# SCH_CPU.net
KiCad netlist of a schematic drawn in Altium Designer
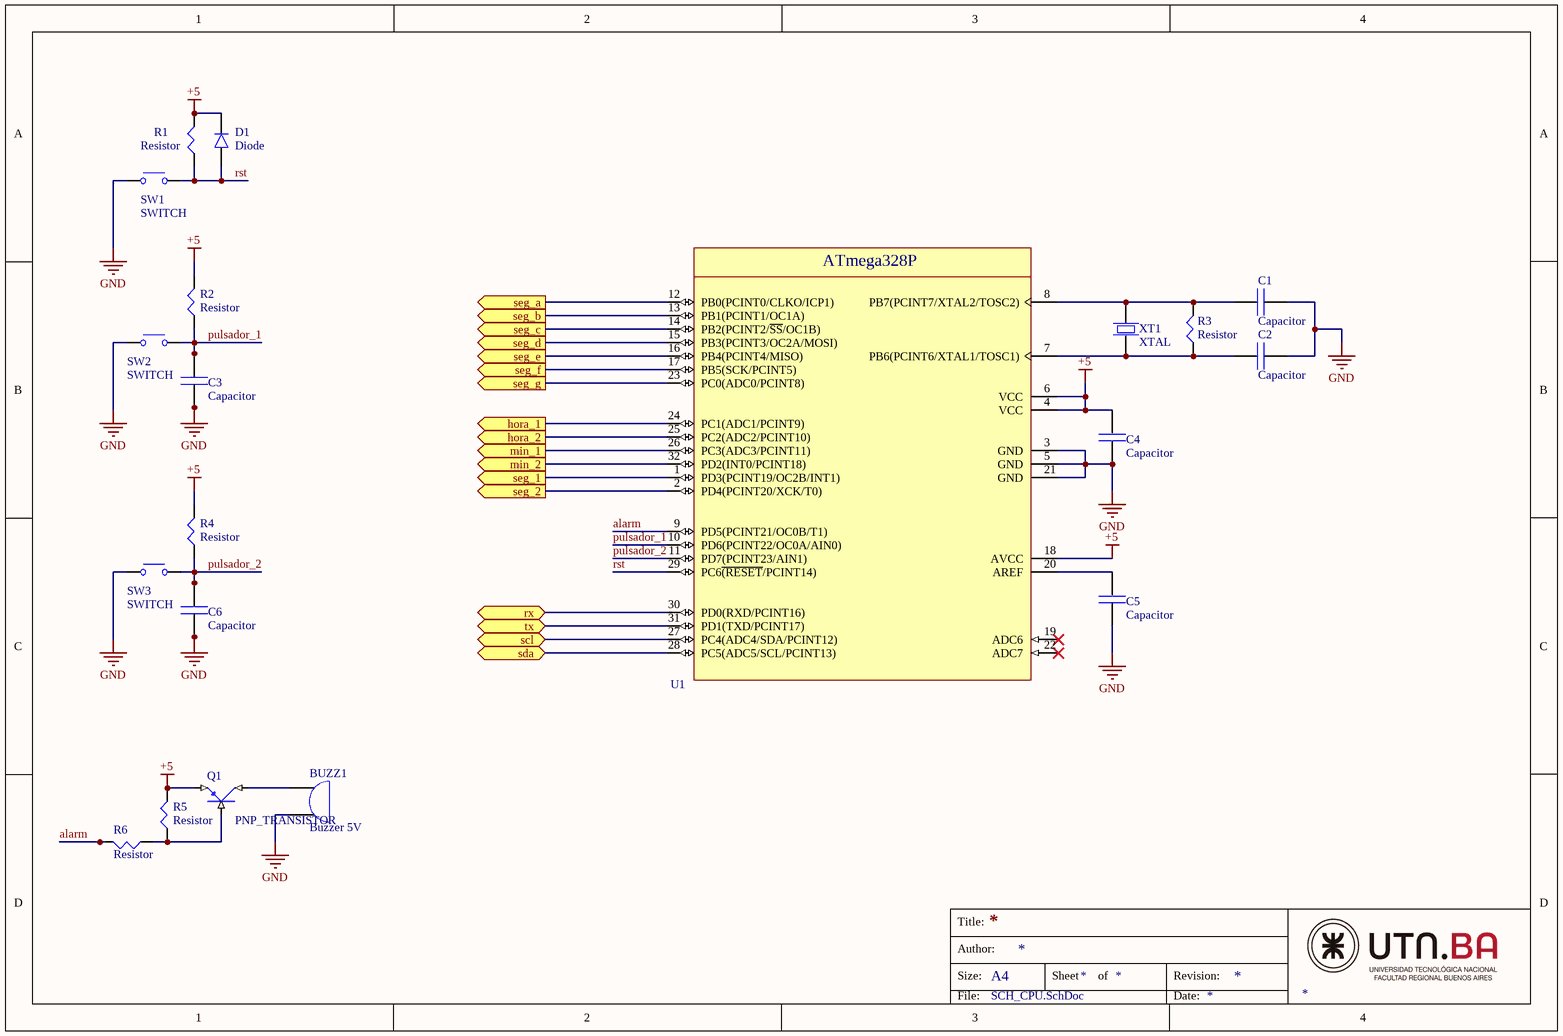
[diagram p0: SCH_CPU.SchDoc]

(export (version "E")
  (design (tool "Eeschema 10.0.6"))
  (components
    (comp (ref "BUZZ1") (value "Buzzer 5V") (libsource (lib "SCH_LIB") (part "Buzzer")))
    (comp (ref "C1")
      (value "Capacitor")
      (description "100nF x 50v")
      (libsource (lib "SCH_LIB") (part "Capacitor"))
    )
    (comp (ref "C2")
      (value "Capacitor")
      (description "100nF x 50v")
      (libsource (lib "SCH_LIB") (part "Capacitor"))
    )
    (comp (ref "C3")
      (value "Capacitor")
      (description "100nF x 50v")
      (libsource (lib "SCH_LIB") (part "Capacitor"))
    )
    (comp (ref "C4")
      (value "Capacitor")
      (description "100nF x 50v")
      (libsource (lib "SCH_LIB") (part "Capacitor"))
    )
    (comp (ref "C5")
      (value "Capacitor")
      (description "100nF x 50v")
      (libsource (lib "SCH_LIB") (part "Capacitor"))
    )
    (comp (ref "C6")
      (value "Capacitor")
      (description "100nF x 50v")
      (libsource (lib "SCH_LIB") (part "Capacitor"))
    )
    (comp (ref "D1") (value "Diode") (description "Signal Diode") (libsource (lib "SCH_LIB") (part "Diode")))
    (comp (ref "Q1") (value "PNP_TRANSISTOR") (libsource (lib "SCH_LIB") (part "PNP_TRANSISTOR")))
    (comp (ref "R1") (value "Resistor") (libsource (lib "SCH_LIB") (part "Resistor")))
    (comp (ref "R2") (value "Resistor") (libsource (lib "SCH_LIB") (part "Resistor")))
    (comp (ref "R3") (value "Resistor") (libsource (lib "SCH_LIB") (part "Resistor")))
    (comp (ref "R4") (value "Resistor") (libsource (lib "SCH_LIB") (part "Resistor")))
    (comp (ref "R5") (value "Resistor") (libsource (lib "SCH_LIB") (part "Resistor")))
    (comp (ref "R6") (value "Resistor") (libsource (lib "SCH_LIB") (part "Resistor")))
    (comp (ref "SW1") (value "SWITCH") (description "NO Switch") (libsource (lib "SCH_LIB") (part "SWITCH")))
    (comp (ref "SW2") (value "SWITCH") (description "NO Switch") (libsource (lib "SCH_LIB") (part "SWITCH")))
    (comp (ref "SW3") (value "SWITCH") (description "NO Switch") (libsource (lib "SCH_LIB") (part "SWITCH")))
    (comp (ref "U1")
      (value "ATmega328P")
      (description "Microcontroller")
      (libsource (lib "SCH_LIB") (part "ATmega328P"))
    )
    (comp (ref "XT1")
      (value "XTAL")
      (description "crystal piezoelectric")
      (libsource (lib "SCH_LIB") (part "XTAL"))
    )
  )
  (nets
    (net (code "1") (name "+5") (class "Default")
      (node (ref "C4") (pin "39") (pinfunction "39_39") (pintype "passive"))
      (node (ref "D1") (pin "35") (pinfunction "35_35") (pintype "passive"))
      (node (ref "Q1") (pin "3") (pinfunction "E_3") (pintype "input"))
      (node (ref "R1") (pin "48") (pinfunction "48_48") (pintype "passive"))
      (node (ref "R2") (pin "48") (pinfunction "48_48") (pintype "passive"))
      (node (ref "R4") (pin "48") (pinfunction "48_48") (pintype "passive"))
      (node (ref "R5") (pin "48") (pinfunction "48_48") (pintype "passive"))
      (node (ref "U1") (pin "18") (pinfunction "AVCC_18") (pintype "power_in"))
      (node (ref "U1") (pin "4") (pinfunction "VCC_4") (pintype "power_in"))
      (node (ref "U1") (pin "6") (pinfunction "VCC_6") (pintype "power_in"))
    )
    (net (code "2") (name "/alarm") (class "Default")
      (node (ref "R6") (pin "48") (pinfunction "48_48") (pintype "passive"))
      (node (ref "U1") (pin "9") (pinfunction "PD5(PCINT21/OC0B/T1)_9") (pintype "bidirectional"))
    )
    (net (code "3") (name "/hora_1") (class "Default")
      (node (ref "U1") (pin "24") (pinfunction "PC1(ADC1/PCINT9)_24") (pintype "bidirectional"))
    )
    (net (code "4") (name "/hora_2") (class "Default")
      (node (ref "U1") (pin "25") (pinfunction "PC2(ADC2/PCINT10)_25") (pintype "bidirectional"))
    )
    (net (code "5") (name "/min_1") (class "Default")
      (node (ref "U1") (pin "26") (pinfunction "PC3(ADC3/PCINT11)_26") (pintype "bidirectional"))
    )
    (net (code "6") (name "/min_2") (class "Default")
      (node (ref "U1") (pin "32") (pinfunction "PD2(INT0/PCINT18)_32") (pintype "bidirectional"))
    )
    (net (code "7") (name "/pulsador_1") (class "Default")
      (node (ref "C3") (pin "39") (pinfunction "39_39") (pintype "passive"))
      (node (ref "R2") (pin "47") (pinfunction "47_47") (pintype "passive"))
      (node (ref "SW2") (pin "6") (pinfunction "6_6") (pintype "passive"))
      (node (ref "U1") (pin "10") (pinfunction "PD6(PCINT22/OC0A/AIN0)_10") (pintype "bidirectional"))
    )
    (net (code "8") (name "/pulsador_2") (class "Default")
      (node (ref "C6") (pin "39") (pinfunction "39_39") (pintype "passive"))
      (node (ref "R4") (pin "47") (pinfunction "47_47") (pintype "passive"))
      (node (ref "SW3") (pin "6") (pinfunction "6_6") (pintype "passive"))
      (node (ref "U1") (pin "11") (pinfunction "PD7(PCINT23/AIN1)_11") (pintype "bidirectional"))
    )
    (net (code "9") (name "/rst") (class "Default")
      (node (ref "D1") (pin "34") (pinfunction "34_34") (pintype "passive"))
      (node (ref "R1") (pin "47") (pinfunction "47_47") (pintype "passive"))
      (node (ref "SW1") (pin "6") (pinfunction "6_6") (pintype "passive"))
      (node (ref "U1") (pin "29") (pinfunction "PC6~{(RESET}/PCINT14)_29") (pintype "bidirectional"))
    )
    (net (code "10") (name "/rx") (class "Default")
      (node (ref "U1") (pin "30") (pinfunction "PD0(RXD/PCINT16)_30") (pintype "bidirectional"))
    )
    (net (code "11") (name "/scl") (class "Default")
      (node (ref "U1") (pin "27") (pinfunction "PC4(ADC4/SDA/PCINT12)_27") (pintype "bidirectional"))
    )
    (net (code "12") (name "/sda") (class "Default")
      (node (ref "U1") (pin "28") (pinfunction "PC5(ADC5/SCL/PCINT13)_28") (pintype "bidirectional"))
    )
    (net (code "13") (name "/seg_1") (class "Default")
      (node (ref "U1") (pin "1") (pinfunction "PD3(PCINT19/OC2B/INT1)_1") (pintype "bidirectional"))
    )
    (net (code "14") (name "/seg_2") (class "Default")
      (node (ref "U1") (pin "2") (pinfunction "PD4(PCINT20/XCK/T0)_2") (pintype "bidirectional"))
    )
    (net (code "15") (name "/seg_a") (class "Default")
      (node (ref "U1") (pin "12") (pinfunction "PB0(PCINT0/CLKO/ICP1)_12") (pintype "bidirectional"))
    )
    (net (code "16") (name "/seg_b") (class "Default")
      (node (ref "U1") (pin "13") (pinfunction "PB1(PCINT1/OC1A)_13") (pintype "bidirectional"))
    )
    (net (code "17") (name "/seg_c") (class "Default")
      (node (ref "U1") (pin "14") (pinfunction "PB2(PCINT2/~{SS}/OC1B)_14") (pintype "bidirectional"))
    )
    (net (code "18") (name "/seg_d") (class "Default")
      (node (ref "U1") (pin "15") (pinfunction "PB3(PCINT3/OC2A/MOSI)_15") (pintype "bidirectional"))
    )
    (net (code "19") (name "/seg_e") (class "Default")
      (node (ref "U1") (pin "16") (pinfunction "PB4(PCINT4/MISO)_16") (pintype "bidirectional"))
    )
    (net (code "20") (name "/seg_f") (class "Default")
      (node (ref "U1") (pin "17") (pinfunction "PB5(SCK/PCINT5)_17") (pintype "bidirectional"))
    )
    (net (code "21") (name "/seg_g") (class "Default")
      (node (ref "U1") (pin "23") (pinfunction "PC0(ADC0/PCINT8)_23") (pintype "bidirectional"))
    )
    (net (code "22") (name "/tx") (class "Default")
      (node (ref "U1") (pin "31") (pinfunction "PD1(TXD/PCINT17)_31") (pintype "bidirectional"))
    )
    (net (code "23") (name "GND") (class "Default")
      (node (ref "BUZZ1") (pin "27") (pinfunction "27_27") (pintype "passive"))
      (node (ref "C1") (pin "38") (pinfunction "38_38") (pintype "passive"))
      (node (ref "C2") (pin "38") (pinfunction "38_38") (pintype "passive"))
      (node (ref "C3") (pin "38") (pinfunction "38_38") (pintype "passive"))
      (node (ref "C4") (pin "38") (pinfunction "38_38") (pintype "passive"))
      (node (ref "C5") (pin "38") (pinfunction "38_38") (pintype "passive"))
      (node (ref "C6") (pin "38") (pinfunction "38_38") (pintype "passive"))
      (node (ref "SW1") (pin "7") (pinfunction "7_7") (pintype "passive"))
      (node (ref "SW2") (pin "7") (pinfunction "7_7") (pintype "passive"))
      (node (ref "SW3") (pin "7") (pinfunction "7_7") (pintype "passive"))
      (node (ref "U1") (pin "21") (pinfunction "GND_21") (pintype "power_in"))
      (node (ref "U1") (pin "3") (pinfunction "GND_3") (pintype "power_in"))
      (node (ref "U1") (pin "5") (pinfunction "GND_5") (pintype "power_in"))
    )
    (net (code "24") (name "Net-(Q1-B)") (class "Default")
      (node (ref "Q1") (pin "1") (pinfunction "B_1") (pintype "input"))
      (node (ref "R5") (pin "47") (pinfunction "47_47") (pintype "passive"))
      (node (ref "R6") (pin "47") (pinfunction "47_47") (pintype "passive"))
    )
    (net (code "25") (name "Net-(Q1-C)") (class "Default")
      (node (ref "BUZZ1") (pin "26") (pinfunction "26_26") (pintype "passive"))
      (node (ref "Q1") (pin "2") (pinfunction "C_2") (pintype "input"))
    )
    (net (code "26") (name "Net-(U1-AREF)") (class "Default")
      (node (ref "C5") (pin "39") (pinfunction "39_39") (pintype "passive"))
      (node (ref "U1") (pin "20") (pinfunction "AREF_20") (pintype "power_in"))
    )
    (net (code "27") (name "Net-(U1-PB6(PCINT6{slash}XTAL1{slash}TOSC1))") (class "Default")
      (node (ref "C2") (pin "39") (pinfunction "39_39") (pintype "passive"))
      (node (ref "R3") (pin "47") (pinfunction "47_47") (pintype "passive"))
      (node (ref "U1") (pin "7") (pinfunction "PB6(PCINT6/XTAL1/TOSC1)_7") (pintype "passive"))
      (node (ref "XT1") (pin "5") (pinfunction "5_5") (pintype "passive"))
    )
    (net (code "28") (name "Net-(U1-PB7(PCINT7{slash}XTAL2{slash}TOSC2))") (class "Default")
      (node (ref "C1") (pin "39") (pinfunction "39_39") (pintype "passive"))
      (node (ref "R3") (pin "48") (pinfunction "48_48") (pintype "passive"))
      (node (ref "U1") (pin "8") (pinfunction "PB7(PCINT7/XTAL2/TOSC2)_8") (pintype "passive"))
      (node (ref "XT1") (pin "4") (pinfunction "4_4") (pintype "passive"))
    )
    (net (code "29") (name "unconnected-(U1-ADC6-Pad19)") (class "Default")
      (node (ref "U1") (pin "19") (pinfunction "ADC6_19") (pintype "input+no_connect"))
    )
    (net (code "30") (name "unconnected-(U1-ADC7-Pad22)") (class "Default")
      (node (ref "U1") (pin "22") (pinfunction "ADC7_22") (pintype "input+no_connect"))
    )
  )
)
